# astronaut_interface.net
KiCad netlist of a schematic drawn in EAGLE
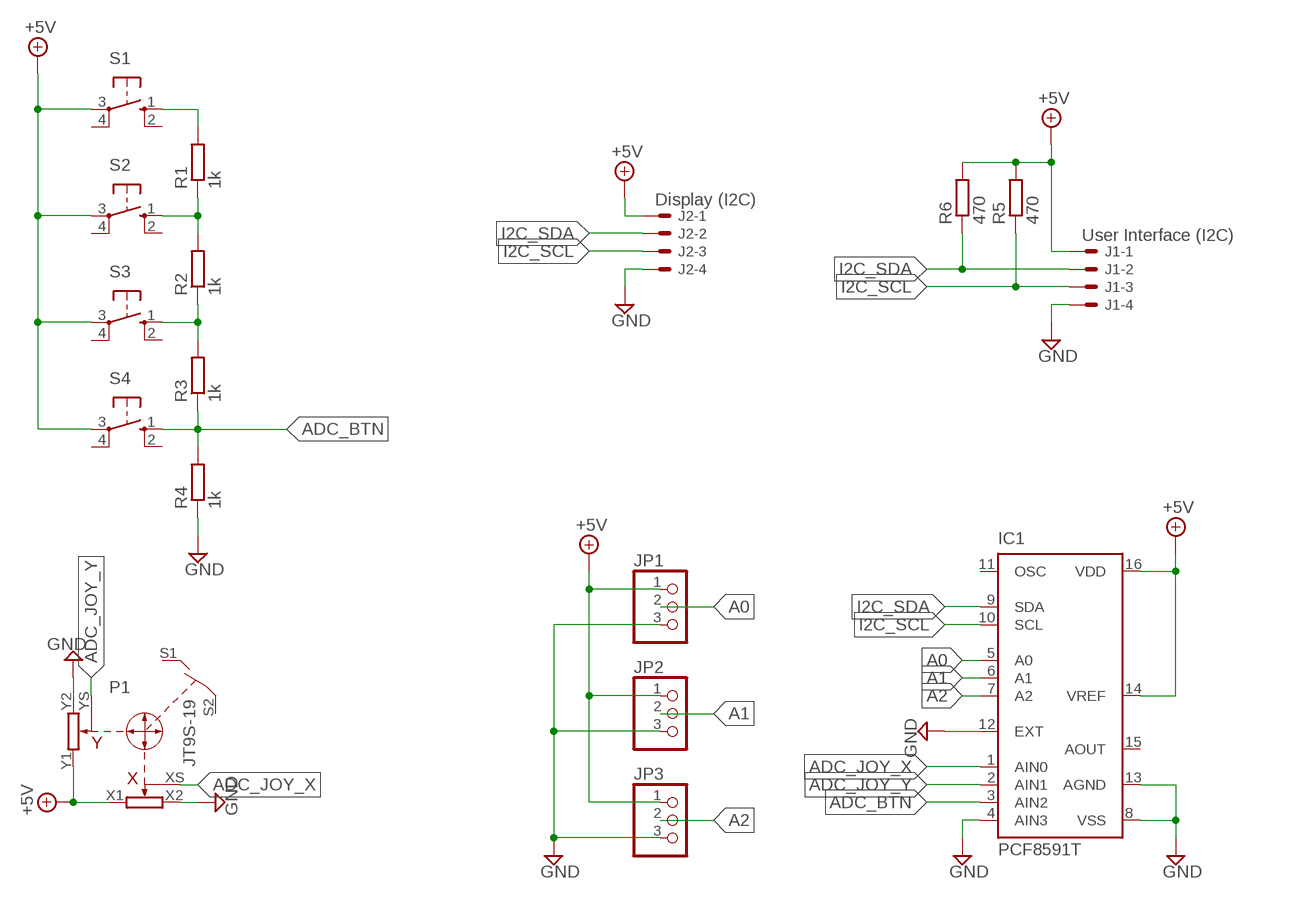
[diagram p0: schematic, sheet 1]

(export (version "E")
  (design (tool "Eeschema 10.0.6"))
  (components
    (comp (ref "IC1")
      (value "PCF8591T")
      (footprint "eagle-import:SO16W")
      (fields (field (name "MPN") "PCF8591T/2,512"))
      (libsource (lib "eagle-import") (part "PCF8591T"))
    )
    (comp (ref "J1")
      (value "User Interface (I2C)")
      (footprint "eagle-import:7395-04")
      (libsource (lib "eagle-import") (part "22-?-0405-7048"))
    )
    (comp (ref "J2")
      (value "Display (I2C)")
      (footprint "eagle-import:7395-04")
      (libsource (lib "eagle-import") (part "22-?-0405-7048"))
    )
    (comp (ref "JP1")
      (value "PINHD-1X3")
      (footprint "eagle-import:1X03")
      (libsource (lib "eagle-import") (part "PINHD-1X3"))
    )
    (comp (ref "JP2")
      (value "PINHD-1X3")
      (footprint "eagle-import:1X03")
      (libsource (lib "eagle-import") (part "PINHD-1X3"))
    )
    (comp (ref "JP3")
      (value "PINHD-1X3")
      (footprint "eagle-import:1X03")
      (libsource (lib "eagle-import") (part "PINHD-1X3"))
    )
    (comp (ref "P1")
      (value "JT9S-19")
      (footprint "eagle-import:JT9S-1P")
      (libsource (lib "eagle-import") (part "JT9S-19"))
    )
    (comp (ref "R1")
      (value "1k")
      (footprint "eagle-import:R0805")
      (libsource (lib "eagle-import") (part "R-EU_R0805"))
    )
    (comp (ref "R2")
      (value "1k")
      (footprint "eagle-import:R0805")
      (libsource (lib "eagle-import") (part "R-EU_R0805"))
    )
    (comp (ref "R3")
      (value "1k")
      (footprint "eagle-import:R0805")
      (libsource (lib "eagle-import") (part "R-EU_R0805"))
    )
    (comp (ref "R4")
      (value "1k")
      (footprint "eagle-import:R0805")
      (libsource (lib "eagle-import") (part "R-EU_R0805"))
    )
    (comp (ref "R5")
      (value "470")
      (footprint "eagle-import:M0805")
      (libsource (lib "eagle-import") (part "resistor_R-EU_M0805"))
    )
    (comp (ref "R6")
      (value "470")
      (footprint "eagle-import:M0805")
      (libsource (lib "eagle-import") (part "resistor_R-EU_M0805"))
    )
    (comp (ref "S1")
      (value "10-XX")
      (footprint "eagle-import:B3F-10XX")
      (fields (field (name "MPN") "B3F-1000"))
      (libsource (lib "eagle-import") (part "10-XX"))
    )
    (comp (ref "S2")
      (value "10-XX")
      (footprint "eagle-import:B3F-10XX")
      (fields (field (name "MPN") "B3F-1000"))
      (libsource (lib "eagle-import") (part "10-XX"))
    )
    (comp (ref "S3")
      (value "10-XX")
      (footprint "eagle-import:B3F-10XX")
      (fields (field (name "MPN") "B3F-1000"))
      (libsource (lib "eagle-import") (part "10-XX"))
    )
    (comp (ref "S4")
      (value "10-XX")
      (footprint "eagle-import:B3F-10XX")
      (fields (field (name "MPN") "B3F-1000"))
      (libsource (lib "eagle-import") (part "10-XX"))
    )
  )
  (nets
    (net (code "1") (name "+5V") (class "Default")
      (node (ref "IC1") (pin "14") (pinfunction "VREF_14") (pintype "input"))
      (node (ref "IC1") (pin "16") (pinfunction "VDD_16") (pintype "power_in"))
      (node (ref "J1") (pin "1") (pinfunction "S_1") (pintype "passive"))
      (node (ref "J2") (pin "1") (pinfunction "S_1") (pintype "passive"))
      (node (ref "JP1") (pin "1") (pinfunction "1_1") (pintype "passive"))
      (node (ref "JP2") (pin "1") (pinfunction "1_1") (pintype "passive"))
      (node (ref "JP3") (pin "1") (pinfunction "1_1") (pintype "passive"))
      (node (ref "P1") (pin "X1") (pinfunction "X1_X1") (pintype "passive"))
      (node (ref "P1") (pin "Y1") (pinfunction "Y1_Y1") (pintype "passive"))
      (node (ref "R5") (pin "2") (pinfunction "2_2") (pintype "passive"))
      (node (ref "R6") (pin "2") (pinfunction "2_2") (pintype "passive"))
      (node (ref "S1") (pin "3") (pinfunction "P_3") (pintype "passive"))
      (node (ref "S2") (pin "3") (pinfunction "P_3") (pintype "passive"))
      (node (ref "S3") (pin "3") (pinfunction "P_3") (pintype "passive"))
      (node (ref "S4") (pin "3") (pinfunction "P_3") (pintype "passive"))
    )
    (net (code "2") (name "A0") (class "Default")
      (node (ref "IC1") (pin "5") (pinfunction "A0_5") (pintype "input"))
      (node (ref "JP1") (pin "2") (pinfunction "2_2") (pintype "passive"))
    )
    (net (code "3") (name "A1") (class "Default")
      (node (ref "IC1") (pin "6") (pinfunction "A1_6") (pintype "input"))
      (node (ref "JP2") (pin "2") (pinfunction "2_2") (pintype "passive"))
    )
    (net (code "4") (name "A2") (class "Default")
      (node (ref "IC1") (pin "7") (pinfunction "A2_7") (pintype "input"))
      (node (ref "JP3") (pin "2") (pinfunction "2_2") (pintype "passive"))
    )
    (net (code "5") (name "ADC_BTN") (class "Default")
      (node (ref "IC1") (pin "3") (pinfunction "AIN2_3") (pintype "input"))
      (node (ref "R3") (pin "1") (pinfunction "1_1") (pintype "passive"))
      (node (ref "R4") (pin "2") (pinfunction "2_2") (pintype "passive"))
      (node (ref "S4") (pin "1") (pinfunction "S_1") (pintype "passive"))
    )
    (net (code "6") (name "ADC_JOY_X") (class "Default")
      (node (ref "IC1") (pin "1") (pinfunction "AIN0_1") (pintype "input"))
      (node (ref "P1") (pin "XS") (pinfunction "XS_XS") (pintype "passive"))
    )
    (net (code "7") (name "ADC_JOY_Y") (class "Default")
      (node (ref "IC1") (pin "2") (pinfunction "AIN1_2") (pintype "input"))
      (node (ref "P1") (pin "YS") (pinfunction "YS_YS") (pintype "passive"))
    )
    (net (code "8") (name "GND") (class "Default")
      (node (ref "IC1") (pin "12") (pinfunction "EXT_12") (pintype "input"))
      (node (ref "IC1") (pin "13") (pinfunction "AGND_13") (pintype "power_in"))
      (node (ref "IC1") (pin "4") (pinfunction "AIN3_4") (pintype "input"))
      (node (ref "IC1") (pin "8") (pinfunction "VSS_8") (pintype "power_in"))
      (node (ref "J1") (pin "4") (pinfunction "S_4") (pintype "passive"))
      (node (ref "J2") (pin "4") (pinfunction "S_4") (pintype "passive"))
      (node (ref "JP1") (pin "3") (pinfunction "3_3") (pintype "passive"))
      (node (ref "JP2") (pin "3") (pinfunction "3_3") (pintype "passive"))
      (node (ref "JP3") (pin "3") (pinfunction "3_3") (pintype "passive"))
      (node (ref "P1") (pin "X2") (pinfunction "X2_X2") (pintype "passive"))
      (node (ref "P1") (pin "Y2") (pinfunction "Y2_Y2") (pintype "passive"))
      (node (ref "R4") (pin "1") (pinfunction "1_1") (pintype "passive"))
    )
    (net (code "9") (name "I2C_SCL") (class "Default")
      (node (ref "IC1") (pin "10") (pinfunction "SCL_10") (pintype "input"))
      (node (ref "J1") (pin "3") (pinfunction "S_3") (pintype "passive"))
      (node (ref "J2") (pin "3") (pinfunction "S_3") (pintype "passive"))
      (node (ref "R5") (pin "1") (pinfunction "1_1") (pintype "passive"))
    )
    (net (code "10") (name "I2C_SDA") (class "Default")
      (node (ref "IC1") (pin "9") (pinfunction "SDA_9") (pintype "bidirectional"))
      (node (ref "J1") (pin "2") (pinfunction "S_2") (pintype "passive"))
      (node (ref "J2") (pin "2") (pinfunction "S_2") (pintype "passive"))
      (node (ref "R6") (pin "1") (pinfunction "1_1") (pintype "passive"))
    )
    (net (code "11") (name "Net-(S1-S)") (class "Default")
      (node (ref "R1") (pin "2") (pinfunction "2_2") (pintype "passive"))
      (node (ref "S1") (pin "1") (pinfunction "S_1") (pintype "passive"))
    )
    (net (code "12") (name "Net-(S2-S)") (class "Default")
      (node (ref "R1") (pin "1") (pinfunction "1_1") (pintype "passive"))
      (node (ref "R2") (pin "2") (pinfunction "2_2") (pintype "passive"))
      (node (ref "S2") (pin "1") (pinfunction "S_1") (pintype "passive"))
    )
    (net (code "13") (name "Net-(S3-S)") (class "Default")
      (node (ref "R2") (pin "1") (pinfunction "1_1") (pintype "passive"))
      (node (ref "R3") (pin "2") (pinfunction "2_2") (pintype "passive"))
      (node (ref "S3") (pin "1") (pinfunction "S_1") (pintype "passive"))
    )
    (net (code "14") (name "unconnected-(IC1-AOUT-Pad15)") (class "Default")
      (node (ref "IC1") (pin "15") (pinfunction "AOUT_15") (pintype "output"))
    )
    (net (code "15") (name "unconnected-(IC1-OSC-Pad11)") (class "Default")
      (node (ref "IC1") (pin "11") (pinfunction "OSC_11") (pintype "input"))
    )
    (net (code "16") (name "unconnected-(P1-PadS1)") (class "Default")
      (node (ref "P1") (pin "S1") (pinfunction "S1_S1") (pintype "passive"))
    )
    (net (code "17") (name "unconnected-(P1-PadS2)") (class "Default")
      (node (ref "P1") (pin "S2") (pinfunction "S2_S2") (pintype "passive"))
    )
    (net (code "18") (name "unconnected-(S1-P1-Pad4)") (class "Default")
      (node (ref "S1") (pin "4") (pinfunction "P1_4") (pintype "passive"))
    )
    (net (code "19") (name "unconnected-(S1-S1-Pad2)") (class "Default")
      (node (ref "S1") (pin "2") (pinfunction "S1_2") (pintype "passive"))
    )
    (net (code "20") (name "unconnected-(S2-P1-Pad4)") (class "Default")
      (node (ref "S2") (pin "4") (pinfunction "P1_4") (pintype "passive"))
    )
    (net (code "21") (name "unconnected-(S2-S1-Pad2)") (class "Default")
      (node (ref "S2") (pin "2") (pinfunction "S1_2") (pintype "passive"))
    )
    (net (code "22") (name "unconnected-(S3-P1-Pad4)") (class "Default")
      (node (ref "S3") (pin "4") (pinfunction "P1_4") (pintype "passive"))
    )
    (net (code "23") (name "unconnected-(S3-S1-Pad2)") (class "Default")
      (node (ref "S3") (pin "2") (pinfunction "S1_2") (pintype "passive"))
    )
    (net (code "24") (name "unconnected-(S4-P1-Pad4)") (class "Default")
      (node (ref "S4") (pin "4") (pinfunction "P1_4") (pintype "passive"))
    )
    (net (code "25") (name "unconnected-(S4-S1-Pad2)") (class "Default")
      (node (ref "S4") (pin "2") (pinfunction "S1_2") (pintype "passive"))
    )
  )
)
